# Nixiespeed2.net
KiCad netlist of a schematic drawn in EAGLE
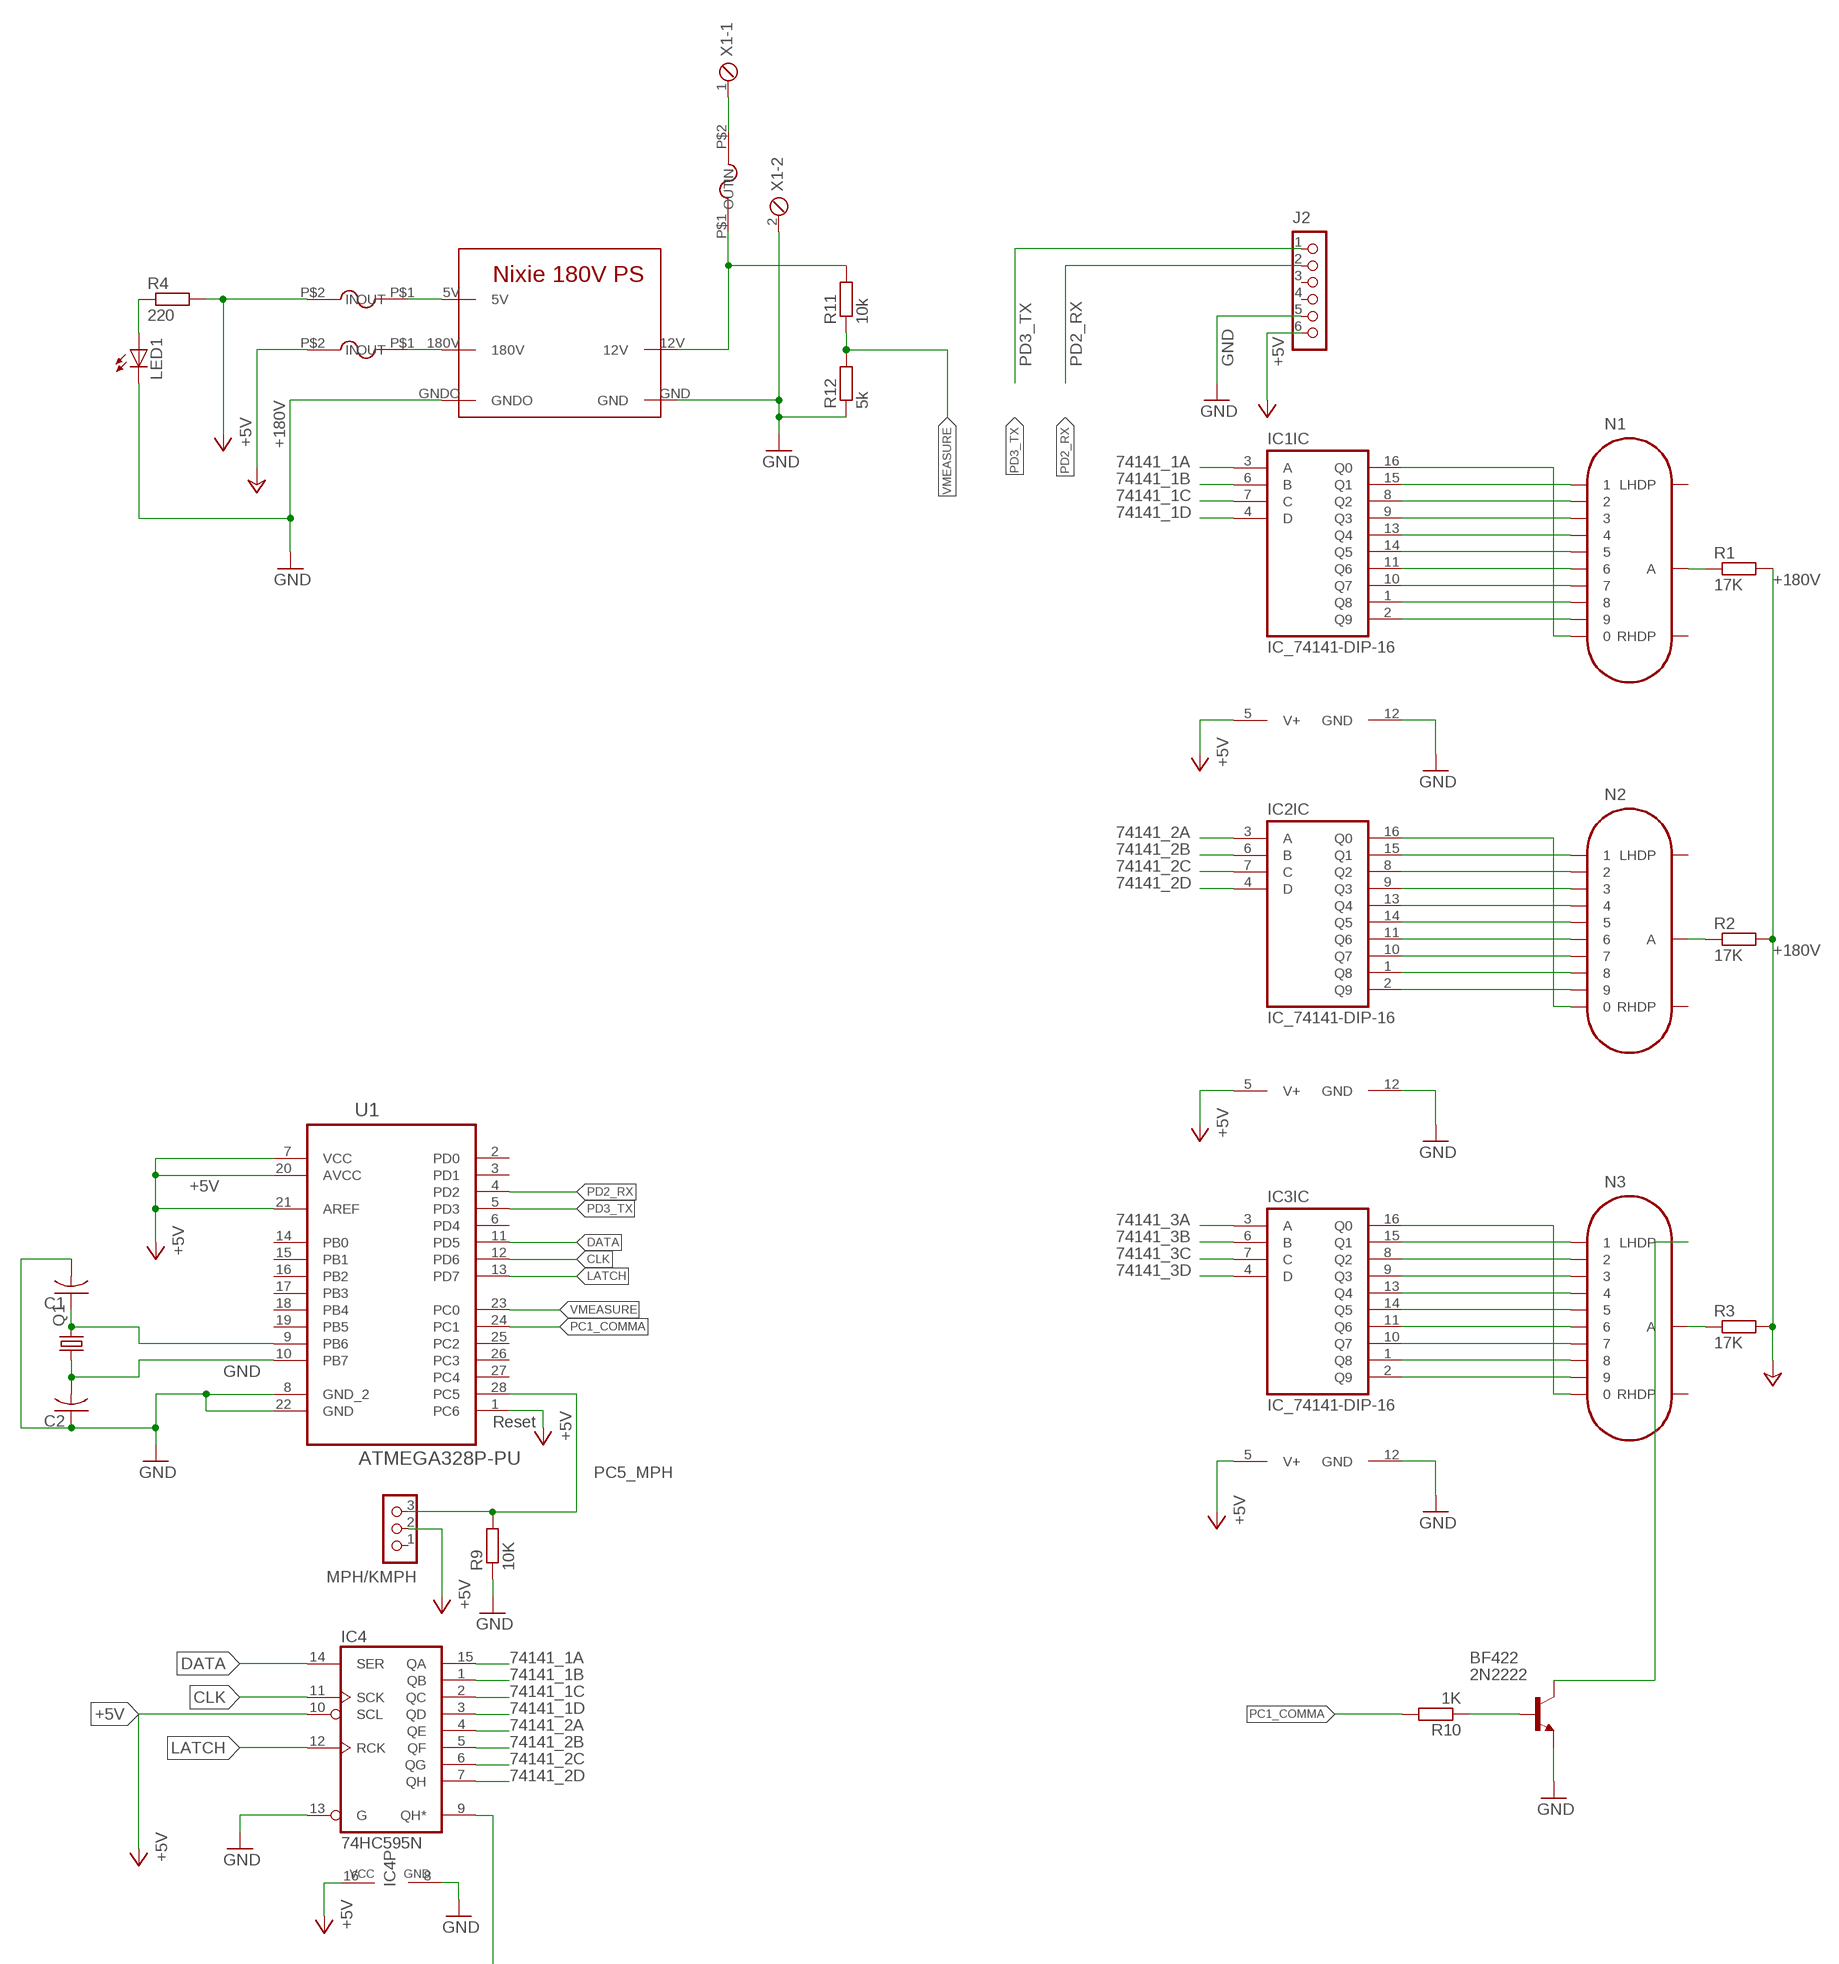
[diagram p0: schematic, sheet 1, part 1 of 2]
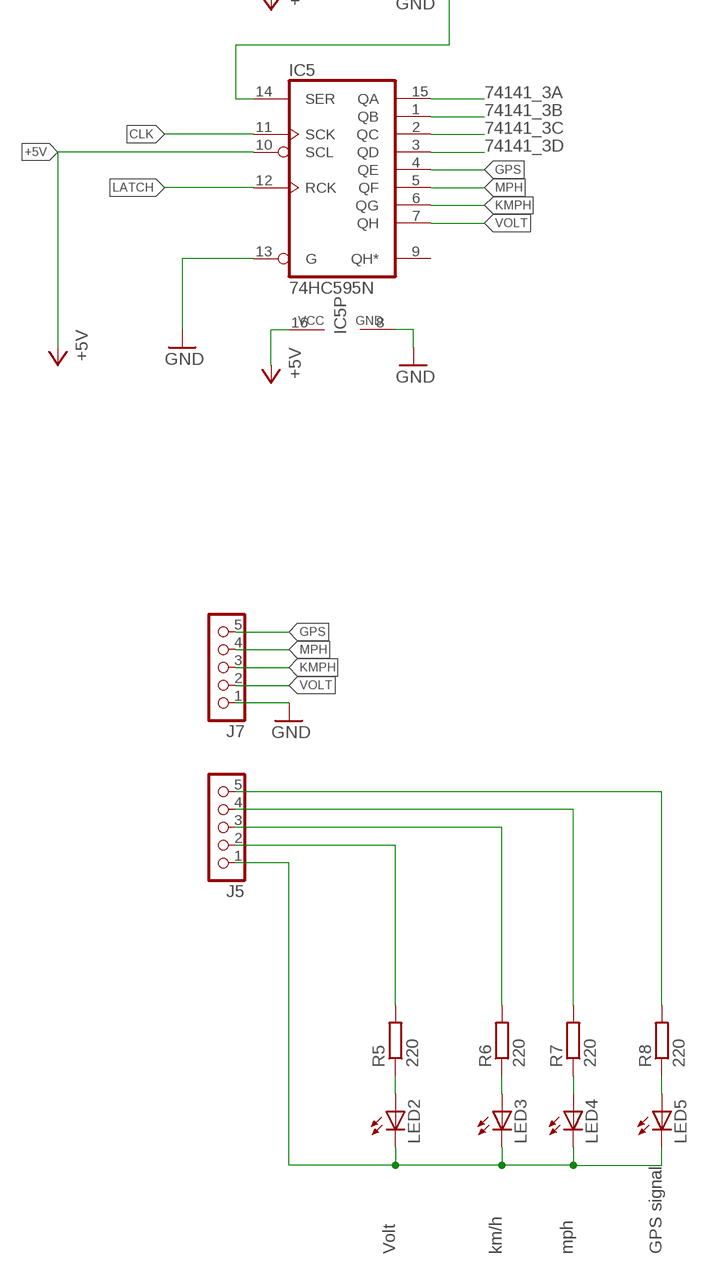
[diagram p1: schematic, sheet 1, part 2 of 2]

(export (version "E")
  (design (tool "Eeschema 10.0.6"))
  (components
    (comp (ref "BF422")
      (value "2N2222")
      (footprint "eagle-import:TO92-EBC-OVAL")
      (libsource (lib "eagle-import") (part "2N2222"))
    )
    (comp (ref "C1")
      (value "C-USC1206")
      (footprint "eagle-import:C1206")
      (libsource (lib "eagle-import") (part "C-USC1206"))
    )
    (comp (ref "C2")
      (value "C-USC1206")
      (footprint "eagle-import:C1206")
      (libsource (lib "eagle-import") (part "C-USC1206"))
    )
    (comp (ref "F2")
      (value "MICROFUSE")
      (footprint "eagle-import:MICROFUSE")
      (libsource (lib "eagle-import") (part "MICROFUSE"))
    )
    (comp (ref "F3")
      (value "MICROFUSE")
      (footprint "eagle-import:MICROFUSE")
      (libsource (lib "eagle-import") (part "MICROFUSE"))
    )
    (comp (ref "IC1")
      (value "IC_74141-DIP-16")
      (footprint "eagle-import:DIL16")
      (libsource (lib "eagle-import") (part "IC_74141-DIP-16"))
    )
    (comp (ref "IC2")
      (value "IC_74141-DIP-16")
      (footprint "eagle-import:DIL16")
      (libsource (lib "eagle-import") (part "IC_74141-DIP-16"))
    )
    (comp (ref "IC3")
      (value "IC_74141-DIP-16")
      (footprint "eagle-import:DIL16")
      (libsource (lib "eagle-import") (part "IC_74141-DIP-16"))
    )
    (comp (ref "IC4")
      (value "74HC595N")
      (footprint "eagle-import:DIL16")
      (libsource (lib "eagle-import") (part "74595NHC"))
    )
    (comp (ref "IC5")
      (value "74HC595N")
      (footprint "eagle-import:DIL16")
      (libsource (lib "eagle-import") (part "74595NHC"))
    )
    (comp (ref "J2")
      (value "CON_HEADER_1X06-PTH")
      (footprint "eagle-import:M1X6")
      (libsource (lib "eagle-import") (part "CON_HEADER_1X06-PTH"))
    )
    (comp (ref "J5")
      (value "CON_HEADER_1X05-PTH")
      (footprint "eagle-import:M1X5")
      (libsource (lib "eagle-import") (part "CON_HEADER_1X05-PTH"))
    )
    (comp (ref "J7")
      (value "CON_HEADER_1X05-PTH")
      (footprint "eagle-import:M1X5")
      (libsource (lib "eagle-import") (part "CON_HEADER_1X05-PTH"))
    )
    (comp (ref "LED1")
      (value "LED3MM")
      (footprint "eagle-import:LED3MM")
      (libsource (lib "eagle-import") (part "LED3MM"))
    )
    (comp (ref "LED2")
      (value "LED3MM")
      (footprint "eagle-import:LED3MM")
      (libsource (lib "eagle-import") (part "LED3MM"))
    )
    (comp (ref "LED3")
      (value "LED3MM")
      (footprint "eagle-import:LED3MM")
      (libsource (lib "eagle-import") (part "LED3MM"))
    )
    (comp (ref "LED4")
      (value "LED3MM")
      (footprint "eagle-import:LED3MM")
      (libsource (lib "eagle-import") (part "LED3MM"))
    )
    (comp (ref "LED5")
      (value "LED3MM")
      (footprint "eagle-import:LED3MM")
      (libsource (lib "eagle-import") (part "LED3MM"))
    )
    (comp (ref "MPH/KMPH")
      (value "CON_HEADER_1X03-PTH")
      (footprint "eagle-import:M1X3")
      (libsource (lib "eagle-import") (part "CON_HEADER_1X03-PTH"))
    )
    (comp (ref "N1")
      (value "IN-14")
      (footprint "eagle-import:IN-14")
      (libsource (lib "eagle-import") (part "IN-14"))
    )
    (comp (ref "N2")
      (value "IN-14")
      (footprint "eagle-import:IN-14")
      (libsource (lib "eagle-import") (part "IN-14"))
    )
    (comp (ref "N3")
      (value "IN-14")
      (footprint "eagle-import:IN-14")
      (libsource (lib "eagle-import") (part "IN-14"))
    )
    (comp (ref "Q1")
      (value "CRYSTALHC49S")
      (footprint "eagle-import:HC49_S")
      (libsource (lib "eagle-import") (part "CRYSTALHC49S"))
    )
    (comp (ref "R1")
      (value "17K")
      (footprint "eagle-import:0204_7")
      (libsource (lib "eagle-import") (part "R-EU_0204/7"))
    )
    (comp (ref "R2")
      (value "17K")
      (footprint "eagle-import:0204_7")
      (libsource (lib "eagle-import") (part "R-EU_0204/7"))
    )
    (comp (ref "R3")
      (value "17K")
      (footprint "eagle-import:0204_7")
      (libsource (lib "eagle-import") (part "R-EU_0204/7"))
    )
    (comp (ref "R4")
      (value "220")
      (footprint "eagle-import:M1206")
      (libsource (lib "eagle-import") (part "R-EU_M1206"))
    )
    (comp (ref "R5")
      (value "220")
      (footprint "eagle-import:M1206")
      (libsource (lib "eagle-import") (part "R-EU_M1206"))
    )
    (comp (ref "R6")
      (value "220")
      (footprint "eagle-import:M1206")
      (libsource (lib "eagle-import") (part "R-EU_M1206"))
    )
    (comp (ref "R7")
      (value "220")
      (footprint "eagle-import:M1206")
      (libsource (lib "eagle-import") (part "R-EU_M1206"))
    )
    (comp (ref "R8")
      (value "220")
      (footprint "eagle-import:M1206")
      (libsource (lib "eagle-import") (part "R-EU_M1206"))
    )
    (comp (ref "R9")
      (value "10K")
      (footprint "eagle-import:M1206")
      (libsource (lib "eagle-import") (part "R-EU_M1206"))
    )
    (comp (ref "R10")
      (value "1K")
      (footprint "eagle-import:M1206")
      (libsource (lib "eagle-import") (part "R-EU_M1206"))
    )
    (comp (ref "R11")
      (value "10k")
      (footprint "eagle-import:M1206")
      (libsource (lib "eagle-import") (part "R-EU_M1206"))
    )
    (comp (ref "R12")
      (value "5k")
      (footprint "eagle-import:M1206")
      (libsource (lib "eagle-import") (part "R-EU_M1206"))
    )
    (comp (ref "U$1")
      (value "NIXIEPS")
      (footprint "eagle-import:NIXIEPS")
      (libsource (lib "eagle-import") (part "NIXIEPS"))
    )
    (comp (ref "U$2")
      (value "MICROFUSE")
      (footprint "eagle-import:MICROFUSE")
      (libsource (lib "eagle-import") (part "MICROFUSE"))
    )
    (comp (ref "U1")
      (value "ATMEGA328P-PU")
      (footprint "eagle-import:DIP254P762X457-28")
      (libsource (lib "eagle-import") (part "ATMEGA328P-PU"))
    )
    (comp (ref "X1")
      (value "MPT2")
      (footprint "eagle-import:2POL254")
      (libsource (lib "eagle-import") (part "MPT2"))
    )
  )
  (nets
    (net (code "1") (name "+5V") (class "Default")
      (node (ref "F2") (pin "P$2") (pinfunction "OUT_P$2") (pintype "bidirectional"))
      (node (ref "IC1") (pin "5") (pinfunction "V+_5") (pintype "power_in"))
      (node (ref "IC2") (pin "5") (pinfunction "V+_5") (pintype "power_in"))
      (node (ref "IC3") (pin "5") (pinfunction "V+_5") (pintype "power_in"))
      (node (ref "IC4") (pin "10") (pinfunction "SCL_10") (pintype "input"))
      (node (ref "IC4") (pin "16") (pinfunction "VCC_16") (pintype "power_in"))
      (node (ref "IC5") (pin "10") (pinfunction "SCL_10") (pintype "input"))
      (node (ref "IC5") (pin "16") (pinfunction "VCC_16") (pintype "power_in"))
      (node (ref "J2") (pin "6") (pinfunction "6_6") (pintype "passive"))
      (node (ref "MPH/KMPH") (pin "2") (pinfunction "2_2") (pintype "bidirectional"))
      (node (ref "R4") (pin "2") (pinfunction "2_2") (pintype "passive"))
      (node (ref "U1") (pin "1") (pinfunction "PC6_1") (pintype "bidirectional"))
      (node (ref "U1") (pin "20") (pinfunction "AVCC_20") (pintype "power_in"))
      (node (ref "U1") (pin "21") (pinfunction "AREF_21") (pintype "input"))
      (node (ref "U1") (pin "7") (pinfunction "VCC_7") (pintype "power_in"))
    )
    (net (code "2") (name "+24V") (class "Default")
      (node (ref "F3") (pin "P$2") (pinfunction "OUT_P$2") (pintype "bidirectional"))
      (node (ref "R1") (pin "2") (pinfunction "2_2") (pintype "passive"))
      (node (ref "R2") (pin "2") (pinfunction "2_2") (pintype "passive"))
      (node (ref "R3") (pin "2") (pinfunction "2_2") (pintype "passive"))
    )
    (net (code "3") (name "/74141_1A") (class "Default")
      (node (ref "IC1") (pin "3") (pinfunction "A_3") (pintype "input"))
      (node (ref "IC4") (pin "15") (pinfunction "QA_15") (pintype "tri_state"))
    )
    (net (code "4") (name "/74141_1B") (class "Default")
      (node (ref "IC1") (pin "6") (pinfunction "B_6") (pintype "input"))
      (node (ref "IC4") (pin "1") (pinfunction "QB_1") (pintype "tri_state"))
    )
    (net (code "5") (name "/74141_1C") (class "Default")
      (node (ref "IC1") (pin "7") (pinfunction "C_7") (pintype "input"))
      (node (ref "IC4") (pin "2") (pinfunction "QC_2") (pintype "tri_state"))
    )
    (net (code "6") (name "/74141_1D") (class "Default")
      (node (ref "IC1") (pin "4") (pinfunction "D_4") (pintype "input"))
      (node (ref "IC4") (pin "3") (pinfunction "QD_3") (pintype "tri_state"))
    )
    (net (code "7") (name "/74141_2A") (class "Default")
      (node (ref "IC2") (pin "3") (pinfunction "A_3") (pintype "input"))
      (node (ref "IC4") (pin "4") (pinfunction "QE_4") (pintype "tri_state"))
    )
    (net (code "8") (name "/74141_2B") (class "Default")
      (node (ref "IC2") (pin "6") (pinfunction "B_6") (pintype "input"))
      (node (ref "IC4") (pin "5") (pinfunction "QF_5") (pintype "tri_state"))
    )
    (net (code "9") (name "/74141_2C") (class "Default")
      (node (ref "IC2") (pin "7") (pinfunction "C_7") (pintype "input"))
      (node (ref "IC4") (pin "6") (pinfunction "QG_6") (pintype "tri_state"))
    )
    (net (code "10") (name "/74141_2D") (class "Default")
      (node (ref "IC2") (pin "4") (pinfunction "D_4") (pintype "input"))
      (node (ref "IC4") (pin "7") (pinfunction "QH_7") (pintype "tri_state"))
    )
    (net (code "11") (name "/74141_3A") (class "Default")
      (node (ref "IC3") (pin "3") (pinfunction "A_3") (pintype "input"))
      (node (ref "IC5") (pin "15") (pinfunction "QA_15") (pintype "tri_state"))
    )
    (net (code "12") (name "/74141_3B") (class "Default")
      (node (ref "IC3") (pin "6") (pinfunction "B_6") (pintype "input"))
      (node (ref "IC5") (pin "1") (pinfunction "QB_1") (pintype "tri_state"))
    )
    (net (code "13") (name "/74141_3C") (class "Default")
      (node (ref "IC3") (pin "7") (pinfunction "C_7") (pintype "input"))
      (node (ref "IC5") (pin "2") (pinfunction "QC_2") (pintype "tri_state"))
    )
    (net (code "14") (name "/74141_3D") (class "Default")
      (node (ref "IC3") (pin "4") (pinfunction "D_4") (pintype "input"))
      (node (ref "IC5") (pin "3") (pinfunction "QD_3") (pintype "tri_state"))
    )
    (net (code "15") (name "/PC5_MPH") (class "Default")
      (node (ref "MPH/KMPH") (pin "3") (pinfunction "3_3") (pintype "bidirectional"))
      (node (ref "R9") (pin "2") (pinfunction "2_2") (pintype "passive"))
      (node (ref "U1") (pin "28") (pinfunction "PC5_28") (pintype "bidirectional"))
    )
    (net (code "16") (name "CLK") (class "Default")
      (node (ref "IC4") (pin "11") (pinfunction "SCK_11") (pintype "input"))
      (node (ref "IC5") (pin "11") (pinfunction "SCK_11") (pintype "input"))
      (node (ref "U1") (pin "12") (pinfunction "PD6_12") (pintype "bidirectional"))
    )
    (net (code "17") (name "DATA") (class "Default")
      (node (ref "IC4") (pin "14") (pinfunction "SER_14") (pintype "input"))
      (node (ref "U1") (pin "11") (pinfunction "PD5_11") (pintype "bidirectional"))
    )
    (net (code "18") (name "GND") (class "Default")
      (node (ref "BF422") (pin "E") (pinfunction "E_E") (pintype "passive"))
      (node (ref "C1") (pin "2") (pinfunction "2_2") (pintype "passive"))
      (node (ref "C2") (pin "1") (pinfunction "1_1") (pintype "passive"))
      (node (ref "IC1") (pin "12") (pinfunction "GND_12") (pintype "power_in"))
      (node (ref "IC2") (pin "12") (pinfunction "GND_12") (pintype "power_in"))
      (node (ref "IC3") (pin "12") (pinfunction "GND_12") (pintype "power_in"))
      (node (ref "IC4") (pin "13") (pinfunction "G_13") (pintype "input"))
      (node (ref "IC4") (pin "8") (pinfunction "GND_8") (pintype "power_in"))
      (node (ref "IC5") (pin "13") (pinfunction "G_13") (pintype "input"))
      (node (ref "IC5") (pin "8") (pinfunction "GND_8") (pintype "power_in"))
      (node (ref "J2") (pin "5") (pinfunction "5_5") (pintype "passive"))
      (node (ref "J7") (pin "1") (pinfunction "1_1") (pintype "bidirectional"))
      (node (ref "LED1") (pin "K") (pinfunction "C_K") (pintype "passive"))
      (node (ref "R12") (pin "1") (pinfunction "1_1") (pintype "passive"))
      (node (ref "R9") (pin "1") (pinfunction "1_1") (pintype "passive"))
      (node (ref "U$1") (pin "GND") (pinfunction "GND_GND") (pintype "bidirectional"))
      (node (ref "U$1") (pin "GNDO") (pinfunction "GNDO_GNDO") (pintype "bidirectional"))
      (node (ref "U1") (pin "22") (pinfunction "GND_22") (pintype "passive"))
      (node (ref "U1") (pin "8") (pinfunction "GND_2_8") (pintype "passive"))
      (node (ref "X1") (pin "2") (pinfunction "1_2") (pintype "passive"))
    )
    (net (code "19") (name "GPS") (class "Default")
      (node (ref "IC5") (pin "4") (pinfunction "QE_4") (pintype "tri_state"))
      (node (ref "J7") (pin "5") (pinfunction "5_5") (pintype "bidirectional"))
    )
    (net (code "20") (name "KMPH") (class "Default")
      (node (ref "IC5") (pin "6") (pinfunction "QG_6") (pintype "tri_state"))
      (node (ref "J7") (pin "3") (pinfunction "3_3") (pintype "bidirectional"))
    )
    (net (code "21") (name "LATCH") (class "Default")
      (node (ref "IC4") (pin "12") (pinfunction "RCK_12") (pintype "input"))
      (node (ref "IC5") (pin "12") (pinfunction "RCK_12") (pintype "input"))
      (node (ref "U1") (pin "13") (pinfunction "PD7_13") (pintype "bidirectional"))
    )
    (net (code "22") (name "MPH") (class "Default")
      (node (ref "IC5") (pin "5") (pinfunction "QF_5") (pintype "tri_state"))
      (node (ref "J7") (pin "4") (pinfunction "4_4") (pintype "bidirectional"))
    )
    (net (code "23") (name "Net-(BF422-PadB)") (class "Default")
      (node (ref "BF422") (pin "B") (pinfunction "B_B") (pintype "passive"))
      (node (ref "R10") (pin "1") (pinfunction "1_1") (pintype "passive"))
    )
    (net (code "24") (name "Net-(BF422-PadC)") (class "Default")
      (node (ref "BF422") (pin "C") (pinfunction "C_C") (pintype "passive"))
      (node (ref "N3") (pin "LHDP") (pinfunction "LHDP_LHDP") (pintype "bidirectional"))
    )
    (net (code "25") (name "Net-(F2-IN)") (class "Default")
      (node (ref "F2") (pin "P$1") (pinfunction "IN_P$1") (pintype "bidirectional"))
      (node (ref "U$1") (pin "5V") (pinfunction "5V_5V") (pintype "bidirectional"))
    )
    (net (code "26") (name "Net-(F3-IN)") (class "Default")
      (node (ref "F3") (pin "P$1") (pinfunction "IN_P$1") (pintype "bidirectional"))
      (node (ref "U$1") (pin "180V") (pinfunction "180V_180V") (pintype "bidirectional"))
    )
    (net (code "27") (name "Net-(IC1A-Q0)") (class "Default")
      (node (ref "IC1") (pin "16") (pinfunction "Q0_16") (pintype "output"))
      (node (ref "N1") (pin "0") (pinfunction "0_0") (pintype "bidirectional"))
    )
    (net (code "28") (name "Net-(IC1A-Q1)") (class "Default")
      (node (ref "IC1") (pin "15") (pinfunction "Q1_15") (pintype "output"))
      (node (ref "N1") (pin "1") (pinfunction "1_1") (pintype "bidirectional"))
    )
    (net (code "29") (name "Net-(IC1A-Q2)") (class "Default")
      (node (ref "IC1") (pin "8") (pinfunction "Q2_8") (pintype "output"))
      (node (ref "N1") (pin "2") (pinfunction "2_2") (pintype "bidirectional"))
    )
    (net (code "30") (name "Net-(IC1A-Q3)") (class "Default")
      (node (ref "IC1") (pin "9") (pinfunction "Q3_9") (pintype "output"))
      (node (ref "N1") (pin "3") (pinfunction "3_3") (pintype "bidirectional"))
    )
    (net (code "31") (name "Net-(IC1A-Q4)") (class "Default")
      (node (ref "IC1") (pin "13") (pinfunction "Q4_13") (pintype "output"))
      (node (ref "N1") (pin "4") (pinfunction "4_4") (pintype "bidirectional"))
    )
    (net (code "32") (name "Net-(IC1A-Q5)") (class "Default")
      (node (ref "IC1") (pin "14") (pinfunction "Q5_14") (pintype "output"))
      (node (ref "N1") (pin "5") (pinfunction "5_5") (pintype "bidirectional"))
    )
    (net (code "33") (name "Net-(IC1A-Q6)") (class "Default")
      (node (ref "IC1") (pin "11") (pinfunction "Q6_11") (pintype "output"))
      (node (ref "N1") (pin "6") (pinfunction "6_6") (pintype "bidirectional"))
    )
    (net (code "34") (name "Net-(IC1A-Q7)") (class "Default")
      (node (ref "IC1") (pin "10") (pinfunction "Q7_10") (pintype "output"))
      (node (ref "N1") (pin "7") (pinfunction "7_7") (pintype "bidirectional"))
    )
    (net (code "35") (name "Net-(IC1A-Q8)") (class "Default")
      (node (ref "IC1") (pin "1") (pinfunction "Q8_1") (pintype "output"))
      (node (ref "N1") (pin "8") (pinfunction "8_8") (pintype "bidirectional"))
    )
    (net (code "36") (name "Net-(IC1A-Q9)") (class "Default")
      (node (ref "IC1") (pin "2") (pinfunction "Q9_2") (pintype "output"))
      (node (ref "N1") (pin "9") (pinfunction "9_9") (pintype "bidirectional"))
    )
    (net (code "37") (name "Net-(IC2A-Q0)") (class "Default")
      (node (ref "IC2") (pin "16") (pinfunction "Q0_16") (pintype "output"))
      (node (ref "N2") (pin "0") (pinfunction "0_0") (pintype "bidirectional"))
    )
    (net (code "38") (name "Net-(IC2A-Q1)") (class "Default")
      (node (ref "IC2") (pin "15") (pinfunction "Q1_15") (pintype "output"))
      (node (ref "N2") (pin "1") (pinfunction "1_1") (pintype "bidirectional"))
    )
    (net (code "39") (name "Net-(IC2A-Q2)") (class "Default")
      (node (ref "IC2") (pin "8") (pinfunction "Q2_8") (pintype "output"))
      (node (ref "N2") (pin "2") (pinfunction "2_2") (pintype "bidirectional"))
    )
    (net (code "40") (name "Net-(IC2A-Q3)") (class "Default")
      (node (ref "IC2") (pin "9") (pinfunction "Q3_9") (pintype "output"))
      (node (ref "N2") (pin "3") (pinfunction "3_3") (pintype "bidirectional"))
    )
    (net (code "41") (name "Net-(IC2A-Q4)") (class "Default")
      (node (ref "IC2") (pin "13") (pinfunction "Q4_13") (pintype "output"))
      (node (ref "N2") (pin "4") (pinfunction "4_4") (pintype "bidirectional"))
    )
    (net (code "42") (name "Net-(IC2A-Q5)") (class "Default")
      (node (ref "IC2") (pin "14") (pinfunction "Q5_14") (pintype "output"))
      (node (ref "N2") (pin "5") (pinfunction "5_5") (pintype "bidirectional"))
    )
    (net (code "43") (name "Net-(IC2A-Q6)") (class "Default")
      (node (ref "IC2") (pin "11") (pinfunction "Q6_11") (pintype "output"))
      (node (ref "N2") (pin "6") (pinfunction "6_6") (pintype "bidirectional"))
    )
    (net (code "44") (name "Net-(IC2A-Q7)") (class "Default")
      (node (ref "IC2") (pin "10") (pinfunction "Q7_10") (pintype "output"))
      (node (ref "N2") (pin "7") (pinfunction "7_7") (pintype "bidirectional"))
    )
    (net (code "45") (name "Net-(IC2A-Q8)") (class "Default")
      (node (ref "IC2") (pin "1") (pinfunction "Q8_1") (pintype "output"))
      (node (ref "N2") (pin "8") (pinfunction "8_8") (pintype "bidirectional"))
    )
    (net (code "46") (name "Net-(IC2A-Q9)") (class "Default")
      (node (ref "IC2") (pin "2") (pinfunction "Q9_2") (pintype "output"))
      (node (ref "N2") (pin "9") (pinfunction "9_9") (pintype "bidirectional"))
    )
    (net (code "47") (name "Net-(IC3A-Q0)") (class "Default")
      (node (ref "IC3") (pin "16") (pinfunction "Q0_16") (pintype "output"))
      (node (ref "N3") (pin "0") (pinfunction "0_0") (pintype "bidirectional"))
    )
    (net (code "48") (name "Net-(IC3A-Q1)") (class "Default")
      (node (ref "IC3") (pin "15") (pinfunction "Q1_15") (pintype "output"))
      (node (ref "N3") (pin "1") (pinfunction "1_1") (pintype "bidirectional"))
    )
    (net (code "49") (name "Net-(IC3A-Q2)") (class "Default")
      (node (ref "IC3") (pin "8") (pinfunction "Q2_8") (pintype "output"))
      (node (ref "N3") (pin "2") (pinfunction "2_2") (pintype "bidirectional"))
    )
    (net (code "50") (name "Net-(IC3A-Q3)") (class "Default")
      (node (ref "IC3") (pin "9") (pinfunction "Q3_9") (pintype "output"))
      (node (ref "N3") (pin "3") (pinfunction "3_3") (pintype "bidirectional"))
    )
    (net (code "51") (name "Net-(IC3A-Q4)") (class "Default")
      (node (ref "IC3") (pin "13") (pinfunction "Q4_13") (pintype "output"))
      (node (ref "N3") (pin "4") (pinfunction "4_4") (pintype "bidirectional"))
    )
    (net (code "52") (name "Net-(IC3A-Q5)") (class "Default")
      (node (ref "IC3") (pin "14") (pinfunction "Q5_14") (pintype "output"))
      (node (ref "N3") (pin "5") (pinfunction "5_5") (pintype "bidirectional"))
    )
    (net (code "53") (name "Net-(IC3A-Q6)") (class "Default")
      (node (ref "IC3") (pin "11") (pinfunction "Q6_11") (pintype "output"))
      (node (ref "N3") (pin "6") (pinfunction "6_6") (pintype "bidirectional"))
    )
    (net (code "54") (name "Net-(IC3A-Q7)") (class "Default")
      (node (ref "IC3") (pin "10") (pinfunction "Q7_10") (pintype "output"))
      (node (ref "N3") (pin "7") (pinfunction "7_7") (pintype "bidirectional"))
    )
    (net (code "55") (name "Net-(IC3A-Q8)") (class "Default")
      (node (ref "IC3") (pin "1") (pinfunction "Q8_1") (pintype "output"))
      (node (ref "N3") (pin "8") (pinfunction "8_8") (pintype "bidirectional"))
    )
    (net (code "56") (name "Net-(IC3A-Q9)") (class "Default")
      (node (ref "IC3") (pin "2") (pinfunction "Q9_2") (pintype "output"))
      (node (ref "N3") (pin "9") (pinfunction "9_9") (pintype "bidirectional"))
    )
    (net (code "57") (name "Net-(IC4A-QH*)") (class "Default")
      (node (ref "IC4") (pin "9") (pinfunction "QH*_9") (pintype "tri_state"))
      (node (ref "IC5") (pin "14") (pinfunction "SER_14") (pintype "input"))
    )
    (net (code "58") (name "Net-(J5-Pad2)") (class "Default")
      (node (ref "J5") (pin "2") (pinfunction "2_2") (pintype "bidirectional"))
      (node (ref "R5") (pin "2") (pinfunction "2_2") (pintype "passive"))
    )
    (net (code "59") (name "Net-(J5-Pad3)") (class "Default")
      (node (ref "J5") (pin "3") (pinfunction "3_3") (pintype "bidirectional"))
      (node (ref "R6") (pin "2") (pinfunction "2_2") (pintype "passive"))
    )
    (net (code "60") (name "Net-(J5-Pad4)") (class "Default")
      (node (ref "J5") (pin "4") (pinfunction "4_4") (pintype "bidirectional"))
      (node (ref "R7") (pin "2") (pinfunction "2_2") (pintype "passive"))
    )
    (net (code "61") (name "Net-(J5-Pad5)") (class "Default")
      (node (ref "J5") (pin "5") (pinfunction "5_5") (pintype "bidirectional"))
      (node (ref "R8") (pin "2") (pinfunction "2_2") (pintype "passive"))
    )
    (net (code "62") (name "Net-(LED1-PadA)") (class "Default")
      (node (ref "LED1") (pin "A") (pinfunction "A_A") (pintype "passive"))
      (node (ref "R4") (pin "1") (pinfunction "1_1") (pintype "passive"))
    )
    (net (code "63") (name "Net-(LED2-C)") (class "Default")
      (node (ref "J5") (pin "1") (pinfunction "1_1") (pintype "bidirectional"))
      (node (ref "LED2") (pin "K") (pinfunction "C_K") (pintype "passive"))
      (node (ref "LED3") (pin "K") (pinfunction "C_K") (pintype "passive"))
      (node (ref "LED4") (pin "K") (pinfunction "C_K") (pintype "passive"))
      (node (ref "LED5") (pin "K") (pinfunction "C_K") (pintype "passive"))
    )
    (net (code "64") (name "Net-(LED2-PadA)") (class "Default")
      (node (ref "LED2") (pin "A") (pinfunction "A_A") (pintype "passive"))
      (node (ref "R5") (pin "1") (pinfunction "1_1") (pintype "passive"))
    )
    (net (code "65") (name "Net-(LED3-PadA)") (class "Default")
      (node (ref "LED3") (pin "A") (pinfunction "A_A") (pintype "passive"))
      (node (ref "R6") (pin "1") (pinfunction "1_1") (pintype "passive"))
    )
    (net (code "66") (name "Net-(LED4-PadA)") (class "Default")
      (node (ref "LED4") (pin "A") (pinfunction "A_A") (pintype "passive"))
      (node (ref "R7") (pin "1") (pinfunction "1_1") (pintype "passive"))
    )
    (net (code "67") (name "Net-(LED5-PadA)") (class "Default")
      (node (ref "LED5") (pin "A") (pinfunction "A_A") (pintype "passive"))
      (node (ref "R8") (pin "1") (pinfunction "1_1") (pintype "passive"))
    )
    (net (code "68") (name "Net-(N1-PadA)") (class "Default")
      (node (ref "N1") (pin "A") (pinfunction "A_A") (pintype "bidirectional"))
      (node (ref "R1") (pin "1") (pinfunction "1_1") (pintype "passive"))
    )
    (net (code "69") (name "Net-(N2-PadA)") (class "Default")
      (node (ref "N2") (pin "A") (pinfunction "A_A") (pintype "bidirectional"))
      (node (ref "R2") (pin "1") (pinfunction "1_1") (pintype "passive"))
    )
    (net (code "70") (name "Net-(N3-PadA)") (class "Default")
      (node (ref "N3") (pin "A") (pinfunction "A_A") (pintype "bidirectional"))
      (node (ref "R3") (pin "1") (pinfunction "1_1") (pintype "passive"))
    )
    (net (code "71") (name "Net-(U$2-IN)") (class "Default")
      (node (ref "R11") (pin "2") (pinfunction "2_2") (pintype "passive"))
      (node (ref "U$1") (pin "12V") (pinfunction "12V_12V") (pintype "bidirectional"))
      (node (ref "U$2") (pin "P$1") (pinfunction "IN_P$1") (pintype "bidirectional"))
    )
    (net (code "72") (name "Net-(U$2-OUT)") (class "Default")
      (node (ref "U$2") (pin "P$2") (pinfunction "OUT_P$2") (pintype "bidirectional"))
      (node (ref "X1") (pin "1") (pinfunction "1_1") (pintype "passive"))
    )
    (net (code "73") (name "Net-(U1-PB6)") (class "Default")
      (node (ref "C1") (pin "1") (pinfunction "1_1") (pintype "passive"))
      (node (ref "Q1") (pin "2") (pinfunction "2_2") (pintype "passive"))
      (node (ref "U1") (pin "9") (pinfunction "PB6_9") (pintype "bidirectional"))
    )
    (net (code "74") (name "Net-(U1-PB7)") (class "Default")
      (node (ref "C2") (pin "2") (pinfunction "2_2") (pintype "passive"))
      (node (ref "Q1") (pin "1") (pinfunction "1_1") (pintype "passive"))
      (node (ref "U1") (pin "10") (pinfunction "PB7_10") (pintype "bidirectional"))
    )
    (net (code "75") (name "PC1_COMMA") (class "Default")
      (node (ref "R10") (pin "2") (pinfunction "2_2") (pintype "passive"))
      (node (ref "U1") (pin "24") (pinfunction "PC1_24") (pintype "bidirectional"))
    )
    (net (code "76") (name "PD2_RX") (class "Default")
      (node (ref "J2") (pin "2") (pinfunction "2_2") (pintype "bidirectional"))
      (node (ref "U1") (pin "4") (pinfunction "PD2_4") (pintype "bidirectional"))
    )
    (net (code "77") (name "PD3_TX") (class "Default")
      (node (ref "J2") (pin "1") (pinfunction "1_1") (pintype "bidirectional"))
      (node (ref "U1") (pin "5") (pinfunction "PD3_5") (pintype "bidirectional"))
    )
    (net (code "78") (name "VMEASURE") (class "Default")
      (node (ref "R11") (pin "1") (pinfunction "1_1") (pintype "passive"))
      (node (ref "R12") (pin "2") (pinfunction "2_2") (pintype "passive"))
      (node (ref "U1") (pin "23") (pinfunction "PC0_23") (pintype "bidirectional"))
    )
    (net (code "79") (name "VOLT") (class "Default")
      (node (ref "IC5") (pin "7") (pinfunction "QH_7") (pintype "tri_state"))
      (node (ref "J7") (pin "2") (pinfunction "2_2") (pintype "bidirectional"))
    )
    (net (code "80") (name "unconnected-(IC5A-QH*-Pad9)") (class "Default")
      (node (ref "IC5") (pin "9") (pinfunction "QH*_9") (pintype "tri_state"))
    )
    (net (code "81") (name "unconnected-(J2-Pad3)") (class "Default")
      (node (ref "J2") (pin "3") (pinfunction "3_3") (pintype "passive"))
    )
    (net (code "82") (name "unconnected-(J2-Pad4)") (class "Default")
      (node (ref "J2") (pin "4") (pinfunction "4_4") (pintype "passive"))
    )
    (net (code "83") (name "unconnected-(MPH/KMPH-Pad1)") (class "Default")
      (node (ref "MPH/KMPH") (pin "1") (pinfunction "1_1") (pintype "bidirectional"))
    )
    (net (code "84") (name "unconnected-(N1-PadLHDP)") (class "Default")
      (node (ref "N1") (pin "LHDP") (pinfunction "LHDP_LHDP") (pintype "bidirectional"))
    )
    (net (code "85") (name "unconnected-(N1-PadRHDP)") (class "Default")
      (node (ref "N1") (pin "RHDP") (pinfunction "RHDP_RHDP") (pintype "bidirectional"))
    )
    (net (code "86") (name "unconnected-(N2-PadLHDP)") (class "Default")
      (node (ref "N2") (pin "LHDP") (pinfunction "LHDP_LHDP") (pintype "bidirectional"))
    )
    (net (code "87") (name "unconnected-(N2-PadRHDP)") (class "Default")
      (node (ref "N2") (pin "RHDP") (pinfunction "RHDP_RHDP") (pintype "bidirectional"))
    )
    (net (code "88") (name "unconnected-(N3-PadRHDP)") (class "Default")
      (node (ref "N3") (pin "RHDP") (pinfunction "RHDP_RHDP") (pintype "bidirectional"))
    )
    (net (code "89") (name "unconnected-(U1-PB0-Pad14)") (class "Default")
      (node (ref "U1") (pin "14") (pinfunction "PB0_14") (pintype "bidirectional"))
    )
    (net (code "90") (name "unconnected-(U1-PB1-Pad15)") (class "Default")
      (node (ref "U1") (pin "15") (pinfunction "PB1_15") (pintype "bidirectional"))
    )
    (net (code "91") (name "unconnected-(U1-PB2-Pad16)") (class "Default")
      (node (ref "U1") (pin "16") (pinfunction "PB2_16") (pintype "bidirectional"))
    )
    (net (code "92") (name "unconnected-(U1-PB3-Pad17)") (class "Default")
      (node (ref "U1") (pin "17") (pinfunction "PB3_17") (pintype "bidirectional"))
    )
    (net (code "93") (name "unconnected-(U1-PB4-Pad18)") (class "Default")
      (node (ref "U1") (pin "18") (pinfunction "PB4_18") (pintype "bidirectional"))
    )
    (net (code "94") (name "unconnected-(U1-PB5-Pad19)") (class "Default")
      (node (ref "U1") (pin "19") (pinfunction "PB5_19") (pintype "bidirectional"))
    )
    (net (code "95") (name "unconnected-(U1-PC2-Pad25)") (class "Default")
      (node (ref "U1") (pin "25") (pinfunction "PC2_25") (pintype "bidirectional"))
    )
    (net (code "96") (name "unconnected-(U1-PC3-Pad26)") (class "Default")
      (node (ref "U1") (pin "26") (pinfunction "PC3_26") (pintype "bidirectional"))
    )
    (net (code "97") (name "unconnected-(U1-PC4-Pad27)") (class "Default")
      (node (ref "U1") (pin "27") (pinfunction "PC4_27") (pintype "bidirectional"))
    )
    (net (code "98") (name "unconnected-(U1-PD0-Pad2)") (class "Default")
      (node (ref "U1") (pin "2") (pinfunction "PD0_2") (pintype "bidirectional"))
    )
    (net (code "99") (name "unconnected-(U1-PD1-Pad3)") (class "Default")
      (node (ref "U1") (pin "3") (pinfunction "PD1_3") (pintype "bidirectional"))
    )
    (net (code "100") (name "unconnected-(U1-PD4-Pad6)") (class "Default")
      (node (ref "U1") (pin "6") (pinfunction "PD4_6") (pintype "bidirectional"))
    )
  )
)
